# apple-mini.net
KiCad netlist of a schematic drawn in EAGLE
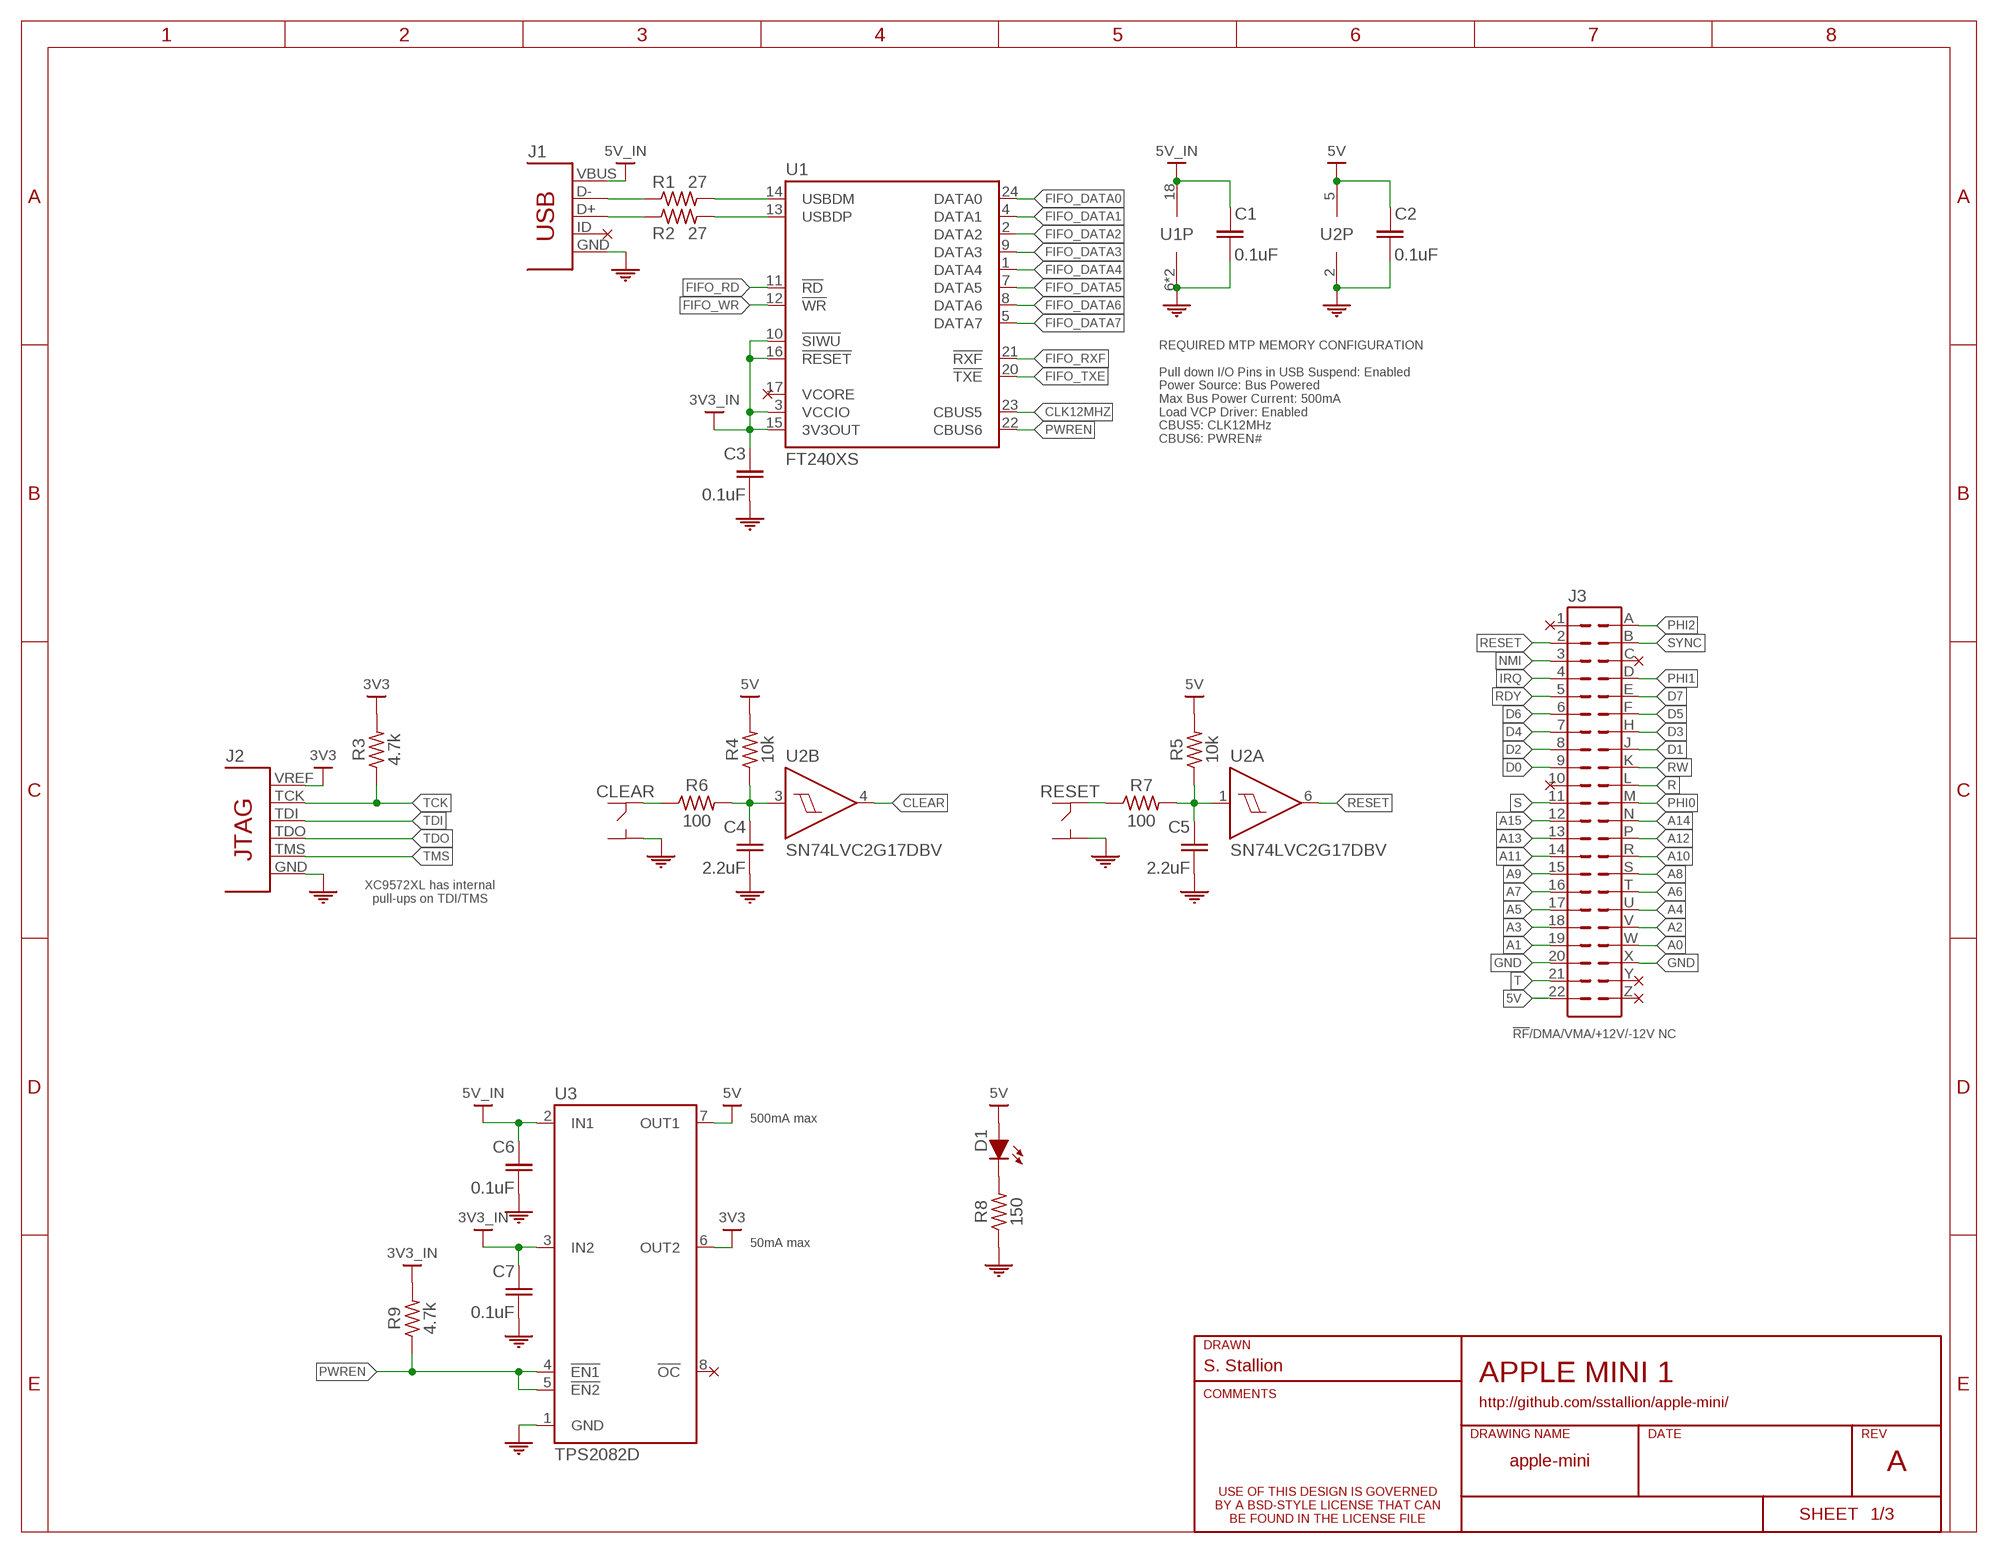
[diagram p0: schematic, sheet 1]
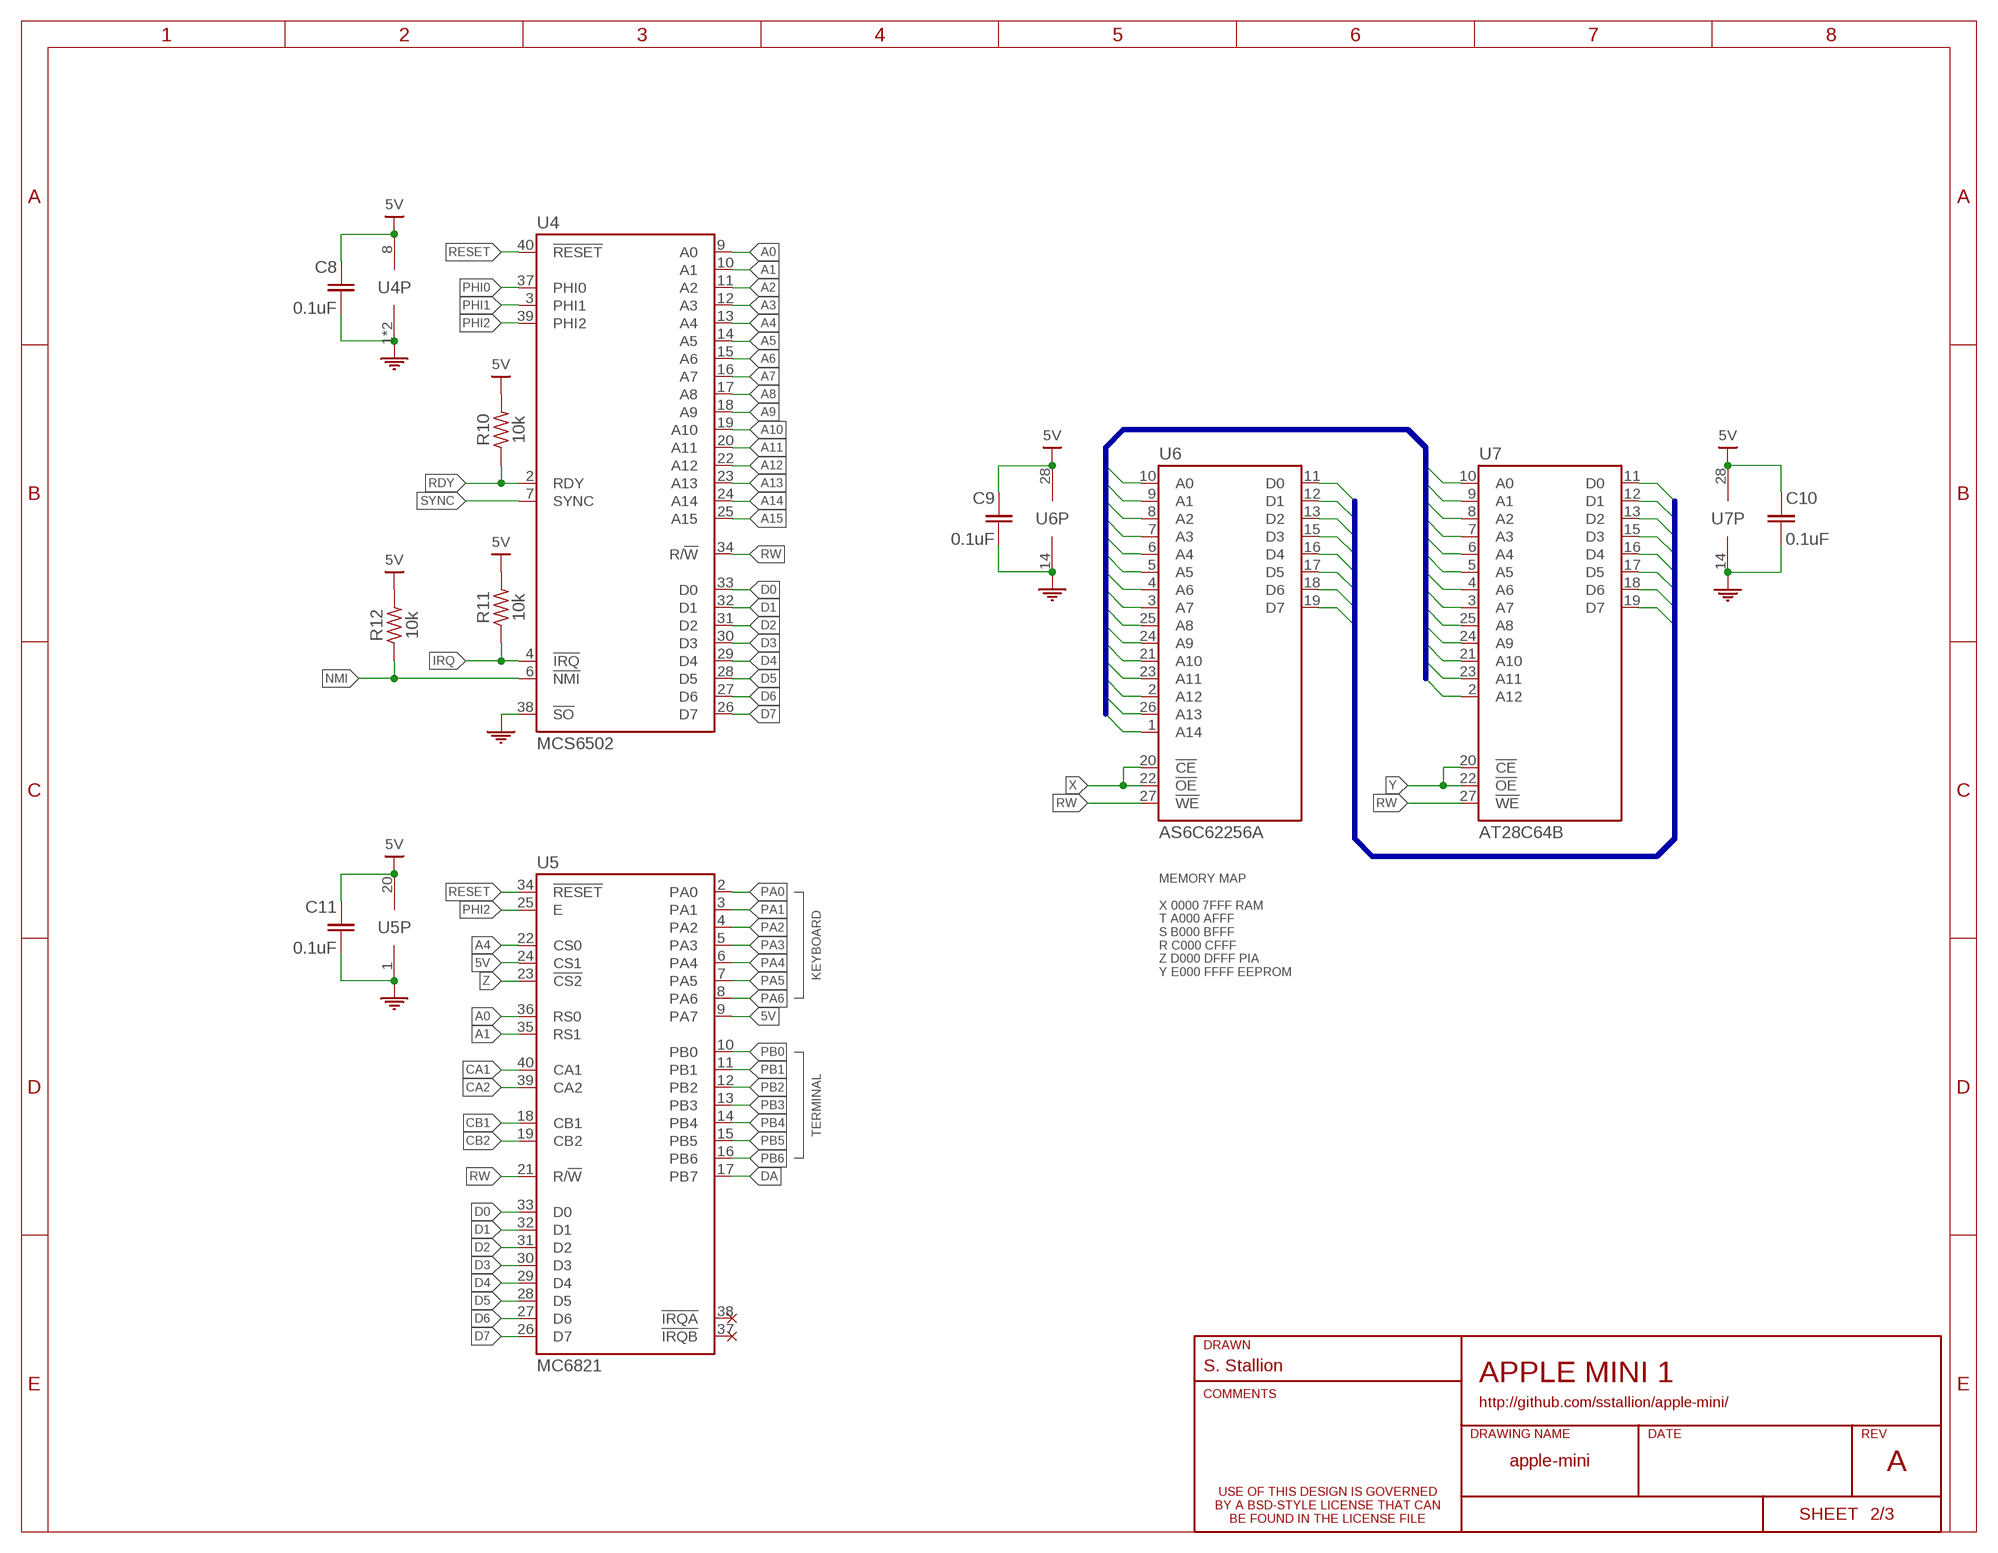
[diagram p1: schematic, sheet 2]
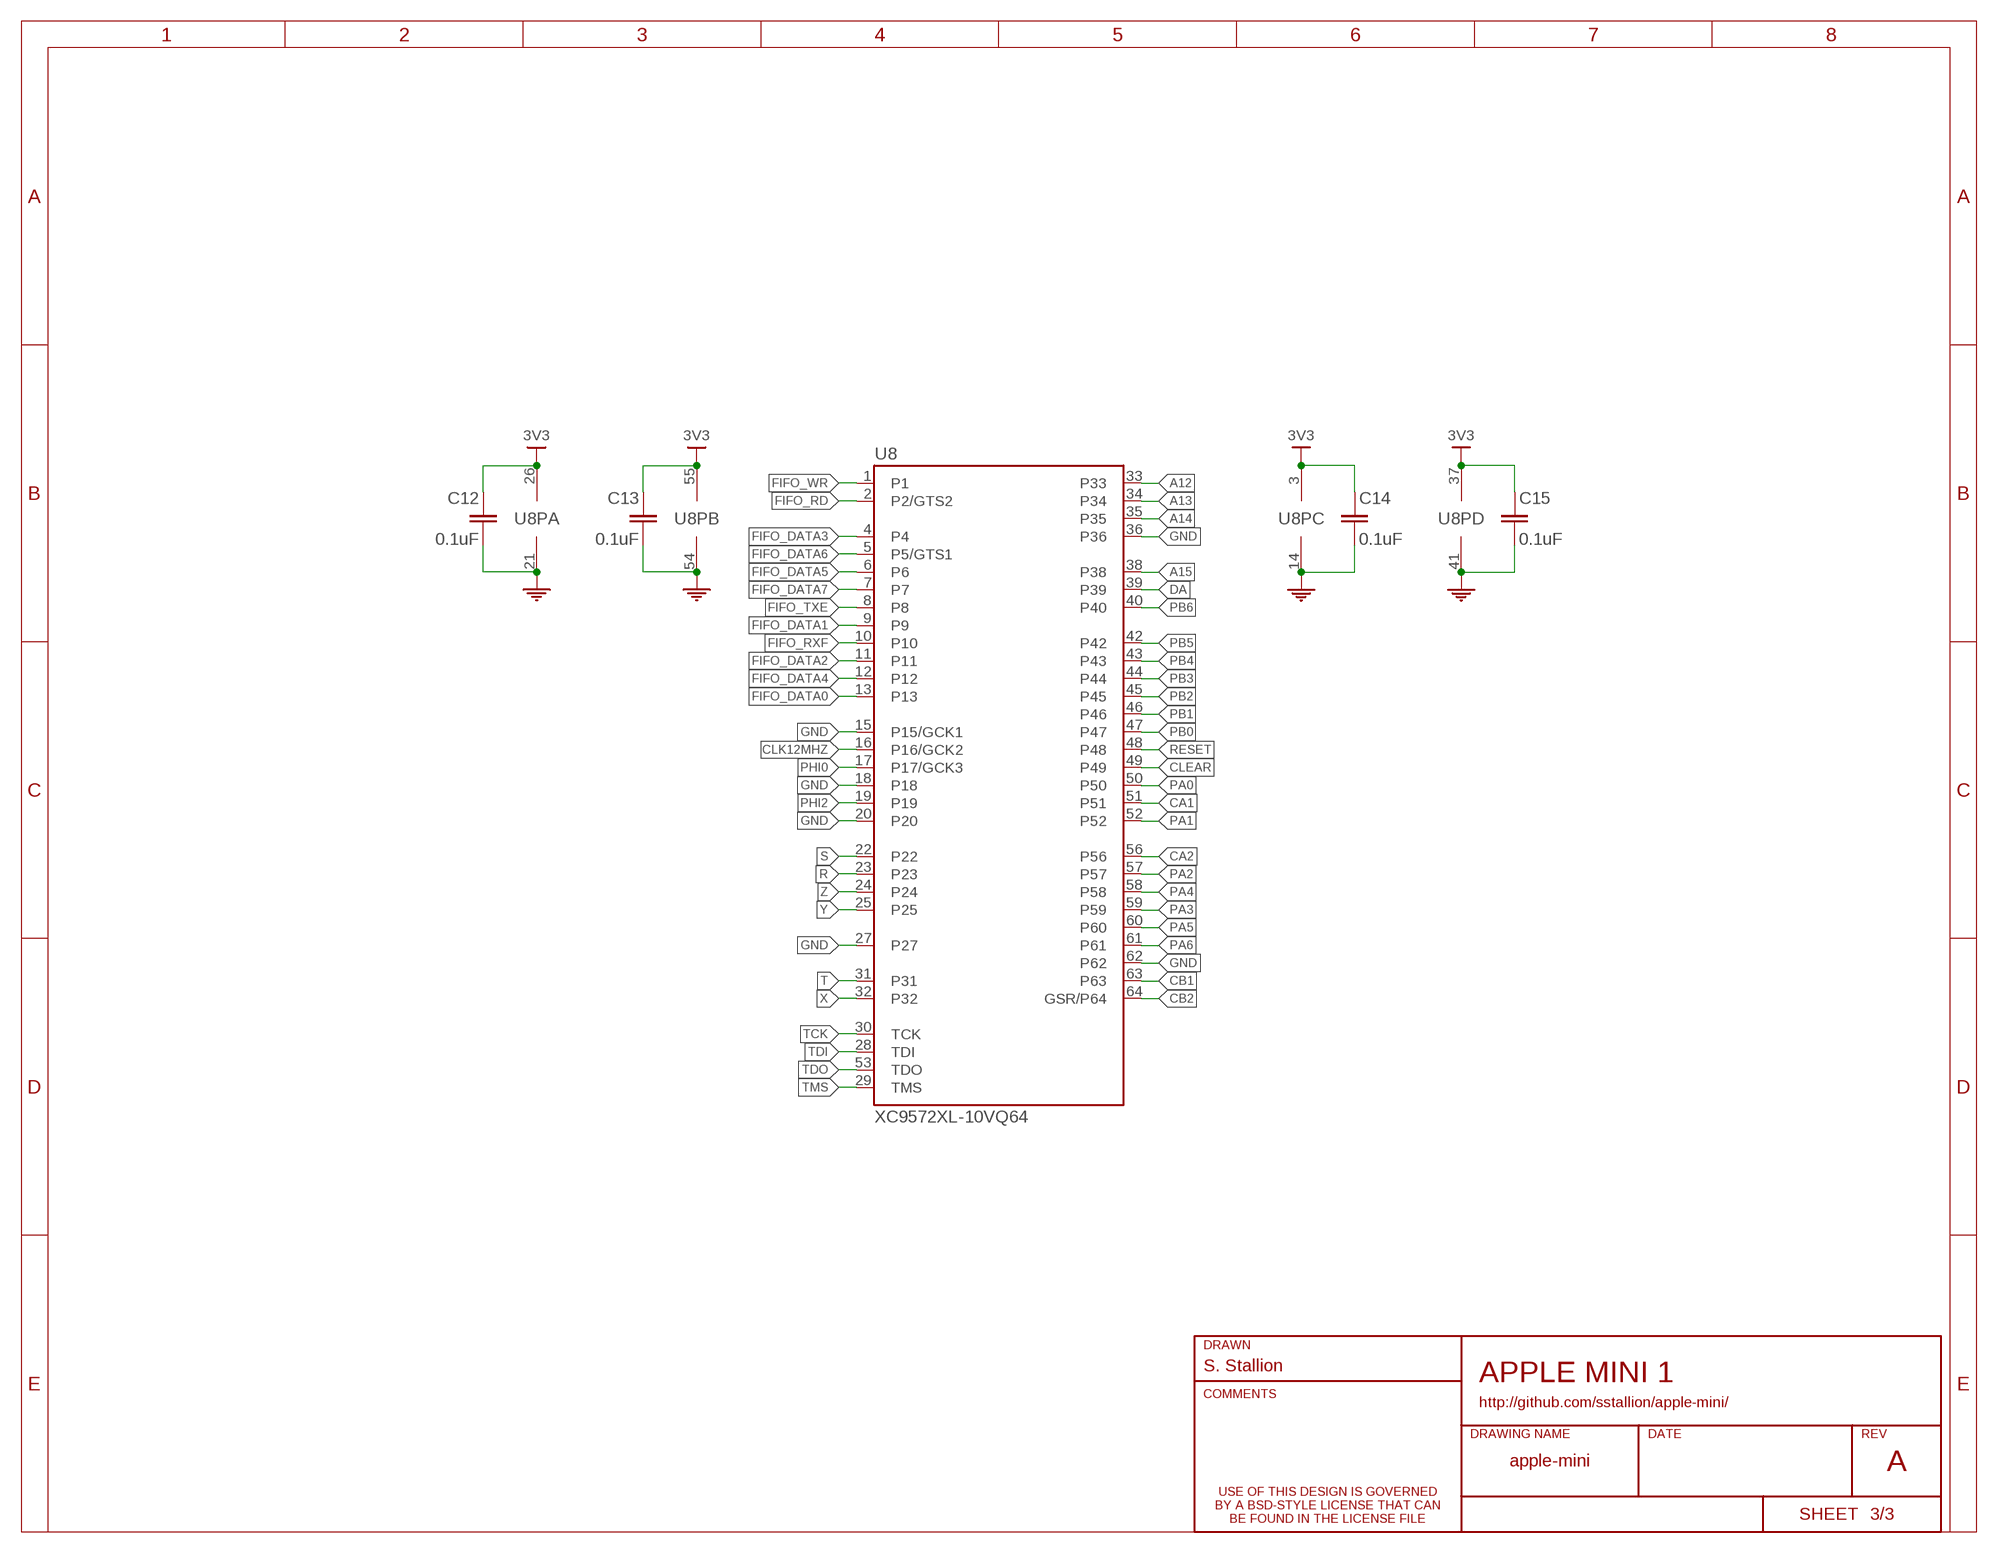
[diagram p2: schematic, sheet 3]

(export (version "E")
  (design (tool "Eeschema 10.0.6"))
  (components
    (comp (ref "C12")
      (value "0.1uF")
      (footprint "eagle-import:0603")
      (fields
        (field (name "COMMENTS") "16V 10% X7R MLCC")
        (field (name "MFR") "Kemet")
        (field (name "MFR_PARTNO") "C0603C104K4RACTU")
        (field (name "VENDOR") "Digi-Key")
        (field (name "VENDOR_PARTNO") "399-1096-1-ND")
      )
      (libsource (lib "eagle-import") (part "C0603"))
    )
    (comp (ref "C13")
      (value "0.1uF")
      (footprint "eagle-import:0603")
      (fields
        (field (name "COMMENTS") "16V 10% X7R MLCC")
        (field (name "MFR") "Kemet")
        (field (name "MFR_PARTNO") "C0603C104K4RACTU")
        (field (name "VENDOR") "Digi-Key")
        (field (name "VENDOR_PARTNO") "399-1096-1-ND")
      )
      (libsource (lib "eagle-import") (part "C0603"))
    )
    (comp (ref "C14")
      (value "0.1uF")
      (footprint "eagle-import:0603")
      (fields
        (field (name "COMMENTS") "16V 10% X7R MLCC")
        (field (name "MFR") "Kemet")
        (field (name "MFR_PARTNO") "C0603C104K4RACTU")
        (field (name "VENDOR") "Digi-Key")
        (field (name "VENDOR_PARTNO") "399-1096-1-ND")
      )
      (libsource (lib "eagle-import") (part "C0603"))
    )
    (comp (ref "C15")
      (value "0.1uF")
      (footprint "eagle-import:0603")
      (fields
        (field (name "COMMENTS") "16V 10% X7R MLCC")
        (field (name "MFR") "Kemet")
        (field (name "MFR_PARTNO") "C0603C104K4RACTU")
        (field (name "VENDOR") "Digi-Key")
        (field (name "VENDOR_PARTNO") "399-1096-1-ND")
      )
      (libsource (lib "eagle-import") (part "C0603"))
    )
    (comp (ref "U8")
      (value "XC9572XL-10VQ64")
      (footprint "eagle-import:VQFP64")
      (fields
        (field (name "MFR") "Xilinx")
        (field (name "MFR_PARTNO") "XC9572XL-10VQG64C")
        (field (name "VENDOR") "Digi-Key")
        (field (name "VENDOR_PARTNO") "122-1388-ND")
      )
      (libsource (lib "eagle-import") (part "XC9572XL-VQ6410"))
    )
    (comp (ref "C8")
      (value "0.1uF")
      (footprint "eagle-import:0603")
      (fields
        (field (name "COMMENTS") "16V 10% X7R MLCC")
        (field (name "MFR") "Kemet")
        (field (name "MFR_PARTNO") "C0603C104K4RACTU")
        (field (name "VENDOR") "Digi-Key")
        (field (name "VENDOR_PARTNO") "399-1096-1-ND")
      )
      (libsource (lib "eagle-import") (part "C0603"))
    )
    (comp (ref "C9")
      (value "0.1uF")
      (footprint "eagle-import:0603")
      (fields
        (field (name "COMMENTS") "16V 10% X7R MLCC")
        (field (name "MFR") "Kemet")
        (field (name "MFR_PARTNO") "C0603C104K4RACTU")
        (field (name "VENDOR") "Digi-Key")
        (field (name "VENDOR_PARTNO") "399-1096-1-ND")
      )
      (libsource (lib "eagle-import") (part "C0603"))
    )
    (comp (ref "C10")
      (value "0.1uF")
      (footprint "eagle-import:0603")
      (fields
        (field (name "COMMENTS") "16V 10% X7R MLCC")
        (field (name "MFR") "Kemet")
        (field (name "MFR_PARTNO") "C0603C104K4RACTU")
        (field (name "VENDOR") "Digi-Key")
        (field (name "VENDOR_PARTNO") "399-1096-1-ND")
      )
      (libsource (lib "eagle-import") (part "C0603"))
    )
    (comp (ref "C11")
      (value "0.1uF")
      (footprint "eagle-import:0603")
      (fields
        (field (name "COMMENTS") "16V 10% X7R MLCC")
        (field (name "MFR") "Kemet")
        (field (name "MFR_PARTNO") "C0603C104K4RACTU")
        (field (name "VENDOR") "Digi-Key")
        (field (name "VENDOR_PARTNO") "399-1096-1-ND")
      )
      (libsource (lib "eagle-import") (part "C0603"))
    )
    (comp (ref "R10")
      (value "10k")
      (footprint "eagle-import:0603")
      (fields
        (field (name "COMMENTS") "5% 1/10W")
        (field (name "MFR") "Yageo")
        (field (name "MFR_PARTNO") "RC0603JR-0710KL")
        (field (name "VENDOR") "Digi-Key")
        (field (name "VENDOR_PARTNO") "311-10KGRCT-ND")
      )
      (libsource (lib "eagle-import") (part "R0603"))
    )
    (comp (ref "R11")
      (value "10k")
      (footprint "eagle-import:0603")
      (fields
        (field (name "COMMENTS") "5% 1/10W")
        (field (name "MFR") "Yageo")
        (field (name "MFR_PARTNO") "RC0603JR-0710KL")
        (field (name "VENDOR") "Digi-Key")
        (field (name "VENDOR_PARTNO") "311-10KGRCT-ND")
      )
      (libsource (lib "eagle-import") (part "R0603"))
    )
    (comp (ref "R12")
      (value "10k")
      (footprint "eagle-import:0603")
      (fields
        (field (name "COMMENTS") "5% 1/10W")
        (field (name "MFR") "Yageo")
        (field (name "MFR_PARTNO") "RC0603JR-0710KL")
        (field (name "VENDOR") "Digi-Key")
        (field (name "VENDOR_PARTNO") "311-10KGRCT-ND")
      )
      (libsource (lib "eagle-import") (part "R0603"))
    )
    (comp (ref "U4")
      (value "MCS6502")
      (footprint "eagle-import:DIP40")
      (fields
        (field (name "MFR") "MOS Technology")
        (field (name "VENDOR") "Jameco")
        (field (name "VENDOR_PARTNO") "43191")
      )
      (libsource (lib "eagle-import") (part "MCS6502"))
    )
    (comp (ref "U5")
      (value "MC6821")
      (footprint "eagle-import:DIP40")
      (fields
        (field (name "MFR") "Motorola")
        (field (name "VENDOR") "Jameco")
        (field (name "VENDOR_PARTNO") "43596")
      )
      (libsource (lib "eagle-import") (part "MC6821"))
    )
    (comp (ref "U6")
      (value "AS6C62256A")
      (footprint "eagle-import:DIP28")
      (fields
        (field (name "MFR") "Alliance Memory")
        (field (name "MFR_PARTNO") "AS6C62256A-70PCN")
        (field (name "VENDOR") "Digi-Key")
        (field (name "VENDOR_PARTNO") "1450-1182-5-ND")
      )
      (libsource (lib "eagle-import") (part "AS6C62256A"))
    )
    (comp (ref "U7")
      (value "AT28C64B")
      (footprint "eagle-import:DIP28")
      (fields
        (field (name "MFR") "Atmel")
        (field (name "MFR_PARTNO") "AT28C64B-15PU")
        (field (name "VENDOR") "Digi-Key")
        (field (name "VENDOR_PARTNO") "AT28C64B-15PU-ND")
      )
      (libsource (lib "eagle-import") (part "AT28C64B"))
    )
    (comp (ref "C1")
      (value "0.1uF")
      (footprint "eagle-import:0603")
      (fields
        (field (name "COMMENTS") "16V 10% X7R MLCC")
        (field (name "MFR") "Kemet")
        (field (name "MFR_PARTNO") "C0603C104K4RACTU")
        (field (name "VENDOR") "Digi-Key")
        (field (name "VENDOR_PARTNO") "399-1096-1-ND")
      )
      (libsource (lib "eagle-import") (part "C0603"))
    )
    (comp (ref "C2")
      (value "0.1uF")
      (footprint "eagle-import:0603")
      (fields
        (field (name "COMMENTS") "16V 10% X7R MLCC")
        (field (name "MFR") "Kemet")
        (field (name "MFR_PARTNO") "C0603C104K4RACTU")
        (field (name "VENDOR") "Digi-Key")
        (field (name "VENDOR_PARTNO") "399-1096-1-ND")
      )
      (libsource (lib "eagle-import") (part "C0603"))
    )
    (comp (ref "C3")
      (value "0.1uF")
      (footprint "eagle-import:0603")
      (fields
        (field (name "COMMENTS") "16V 10% X7R MLCC")
        (field (name "MFR") "Kemet")
        (field (name "MFR_PARTNO") "C0603C104K4RACTU")
        (field (name "VENDOR") "Digi-Key")
        (field (name "VENDOR_PARTNO") "399-1096-1-ND")
      )
      (libsource (lib "eagle-import") (part "C0603"))
    )
    (comp (ref "C4")
      (value "2.2uF")
      (footprint "eagle-import:0603")
      (fields
        (field (name "COMMENTS") "16V 10% X5R MLCC")
        (field (name "MFR") "Kemet")
        (field (name "MFR_PARTNO") "C0603C225K4PACTU")
        (field (name "VENDOR") "Digi-Key")
        (field (name "VENDOR_PARTNO") "399-7886-1-ND")
      )
      (libsource (lib "eagle-import") (part "C0603"))
    )
    (comp (ref "C5")
      (value "2.2uF")
      (footprint "eagle-import:0603")
      (fields
        (field (name "COMMENTS") "16V 10% X5R MLCC")
        (field (name "MFR") "Kemet")
        (field (name "MFR_PARTNO") "C0603C225K4PACTU")
        (field (name "VENDOR") "Digi-Key")
        (field (name "VENDOR_PARTNO") "399-7886-1-ND")
      )
      (libsource (lib "eagle-import") (part "C0603"))
    )
    (comp (ref "C6")
      (value "0.1uF")
      (footprint "eagle-import:0603")
      (fields
        (field (name "COMMENTS") "16V 10% X7R MLCC")
        (field (name "MFR") "Kemet")
        (field (name "MFR_PARTNO") "C0603C104K4RACTU")
        (field (name "VENDOR") "Digi-Key")
        (field (name "VENDOR_PARTNO") "399-1096-1-ND")
      )
      (libsource (lib "eagle-import") (part "C0603"))
    )
    (comp (ref "C7")
      (value "0.1uF")
      (footprint "eagle-import:0603")
      (fields
        (field (name "COMMENTS") "16V 10% X7R MLCC")
        (field (name "MFR") "Kemet")
        (field (name "MFR_PARTNO") "C0603C104K4RACTU")
        (field (name "VENDOR") "Digi-Key")
        (field (name "VENDOR_PARTNO") "399-1096-1-ND")
      )
      (libsource (lib "eagle-import") (part "C0603"))
    )
    (comp (ref "CLEAR")
      (value "TACTSW")
      (footprint "eagle-import:SMTR92")
      (fields
        (field (name "MFR") "C&K Components")
        (field (name "MFR_PARTNO") "PTS645SL50SMTR92 LFS")
        (field (name "COMMENTS") "12V 50mA")
        (field (name "VENDOR") "Digi-Key")
        (field (name "VENDOR_PARTNO") "CKN9088CT-ND")
      )
      (libsource (lib "eagle-import") (part "TACTSW"))
    )
    (comp (ref "D1")
      (value "CHIPLED")
      (footprint "eagle-import:0603")
      (fields
        (field (name "COMMENTS") "2.0-2.5V 20mA")
        (field (name "MFR") "Lite-On")
        (field (name "MFR_PARTNO") "LTST-C190KGKT")
        (field (name "VENDOR") "Digi-Key")
        (field (name "VENDOR_PARTNO") "160-1435-1-ND")
      )
      (libsource (lib "eagle-import") (part "CHIPLED"))
    )
    (comp (ref "J1")
      (value "USBMICRO")
      (footprint "eagle-import:10118193-0001LF")
      (fields
        (field (name "MFR") "FCI")
        (field (name "MFR_PARTNO") "10118193-0001LF")
        (field (name "VENDOR") "Digi-Key")
        (field (name "VENDOR_PARTNO") "609-4616-1-ND")
      )
      (libsource (lib "eagle-import") (part "USBMICRO"))
    )
    (comp (ref "J2")
      (value "JTAG")
      (footprint "eagle-import:PH07-2-SMT")
      (fields
        (field (name "MFR") "Molex")
        (field (name "MFR_PARTNO") "0878321420")
        (field (name "VENDOR") "Digi-Key")
        (field (name "VENDOR_PARTNO") "WM18641-ND")
      )
      (libsource (lib "eagle-import") (part "JTAG"))
    )
    (comp (ref "J3")
      (value "RBM22DRTN")
      (footprint "eagle-import:M22DRTN")
      (fields
        (field (name "MFR") "Sullins")
        (field (name "VENDOR") "Digi-Key")
        (field (name "VENDOR_PARTNO") "RBM22DRTN-ND")
      )
      (libsource (lib "eagle-import") (part "M22DRTNRB"))
    )
    (comp (ref "R1")
      (value "27")
      (footprint "eagle-import:0402")
      (fields
        (field (name "COMMENTS") "5% 1/16W")
        (field (name "MFR") "Yageo")
        (field (name "MFR_PARTNO") "RC0402JR-0727RL")
        (field (name "VENDOR") "Digi-Key")
        (field (name "VENDOR_PARTNO") "311-27JRCT-ND")
      )
      (libsource (lib "eagle-import") (part "R0402"))
    )
    (comp (ref "R2")
      (value "27")
      (footprint "eagle-import:0402")
      (fields
        (field (name "COMMENTS") "5% 1/16W")
        (field (name "MFR") "Yageo")
        (field (name "MFR_PARTNO") "RC0402JR-0727RL")
        (field (name "VENDOR") "Digi-Key")
        (field (name "VENDOR_PARTNO") "311-27JRCT-ND")
      )
      (libsource (lib "eagle-import") (part "R0402"))
    )
    (comp (ref "R3")
      (value "4.7k")
      (footprint "eagle-import:0603")
      (fields
        (field (name "COMMENTS") "5% 1/10W")
        (field (name "MFR") "Yageo")
        (field (name "MFR_PARTNO") "RC0603JR-074K7L")
        (field (name "VENDOR") "Digi-Key")
        (field (name "VENDOR_PARTNO") "311-4.7KGRCT-ND")
      )
      (libsource (lib "eagle-import") (part "R0603"))
    )
    (comp (ref "R4")
      (value "10k")
      (footprint "eagle-import:0603")
      (fields
        (field (name "COMMENTS") "5% 1/10W")
        (field (name "MFR") "Yageo")
        (field (name "MFR_PARTNO") "RC0603JR-0710KL")
        (field (name "VENDOR") "Digi-Key")
        (field (name "VENDOR_PARTNO") "311-10KGRCT-ND")
      )
      (libsource (lib "eagle-import") (part "R0603"))
    )
    (comp (ref "R5")
      (value "10k")
      (footprint "eagle-import:0603")
      (fields
        (field (name "COMMENTS") "5% 1/10W")
        (field (name "MFR") "Yageo")
        (field (name "MFR_PARTNO") "RC0603JR-0710KL")
        (field (name "VENDOR") "Digi-Key")
        (field (name "VENDOR_PARTNO") "311-10KGRCT-ND")
      )
      (libsource (lib "eagle-import") (part "R0603"))
    )
    (comp (ref "R6")
      (value "100")
      (footprint "eagle-import:0603")
      (fields
        (field (name "MFR") "Rohm Semiconductor")
        (field (name "MFR_PARTNO") "ESR03EZPJ101")
        (field (name "VENDOR_PARTNO") "RHM100DCT-ND")
      )
      (libsource (lib "eagle-import") (part "R0603"))
    )
    (comp (ref "R7")
      (value "100")
      (footprint "eagle-import:0603")
      (fields
        (field (name "COMMENTS") "5% 1/4W")
        (field (name "MFR") "Rohm Semiconductor")
        (field (name "MFR_PARTNO") "ESR03EZPJ101")
        (field (name "VENDOR") "Digi-Key")
        (field (name "VENDOR_PARTNO") "RHM100DCT-ND")
      )
      (libsource (lib "eagle-import") (part "R0603"))
    )
    (comp (ref "R8")
      (value "150")
      (footprint "eagle-import:0603")
      (fields
        (field (name "COMMENTS") "5% 1/4W")
        (field (name "MFR") "Rohm Semiconductor")
        (field (name "MFR_PARTNO") "ESR03EZPJ181")
        (field (name "VENDOR") "Digi-Key")
        (field (name "VENDOR_PARTNO") "RHM180DCT-ND")
      )
      (libsource (lib "eagle-import") (part "R0603"))
    )
    (comp (ref "R9")
      (value "4.7k")
      (footprint "eagle-import:0603")
      (fields
        (field (name "COMMENTS") "5% 1/10W")
        (field (name "MFR") "Yageo")
        (field (name "MFR_PARTNO") "RC0603JR-074K7L")
        (field (name "VENDOR") "Digi-Key")
        (field (name "VENDOR_PARTNO") "311-4.7KGRCT-ND")
      )
      (libsource (lib "eagle-import") (part "R0603"))
    )
    (comp (ref "RESET")
      (value "TACTSW")
      (footprint "eagle-import:SMTR92")
      (fields
        (field (name "MFR") "C&K Components")
        (field (name "MFR_PARTNO") "PTS645SL50SMTR92 LFS")
        (field (name "COMMENTS") "12V 50mA")
        (field (name "VENDOR") "Digi-Key")
        (field (name "VENDOR_PARTNO") "CKN9088CT-ND")
      )
      (libsource (lib "eagle-import") (part "TACTSW"))
    )
    (comp (ref "U1")
      (value "FT240XS")
      (footprint "eagle-import:SSOP24")
      (fields
        (field (name "MFR") "FTDI")
        (field (name "MFR_PARTNO") "FT240XS-U")
        (field (name "VENDOR") "Digi-Key")
        (field (name "VENDOR_PARTNO") "768-1158-5-ND")
      )
      (libsource (lib "eagle-import") (part "FT240XS"))
    )
    (comp (ref "U2")
      (value "SN74LVC2G17DBV")
      (footprint "eagle-import:SOT23-6")
      (fields
        (field (name "MFR") "Texas Instruments")
        (field (name "MFR_PARTNO") "SN74LVC2G17DBVR")
        (field (name "VENDOR") "Digi-Key")
        (field (name "VENDOR_PARTNO") "296-13012-1-ND")
      )
      (libsource (lib "eagle-import") (part "SN74LVC2G17DBV"))
    )
    (comp (ref "U3")
      (value "TPS2082D")
      (footprint "eagle-import:SOIC8")
      (fields
        (field (name "MFR") "Texas Instruments")
        (field (name "VENDOR") "Digi-Key")
        (field (name "VENDOR_PARTNO") "296-3433-5-ND")
      )
      (libsource (lib "eagle-import") (part "TPS2082D"))
    )
  )
  (nets
    (net (code "1") (name "3V3") (class "Default")
      (node (ref "C12") (pin "1") (pinfunction "1_1") (pintype "passive"))
      (node (ref "C13") (pin "1") (pinfunction "1_1") (pintype "passive"))
      (node (ref "C14") (pin "1") (pinfunction "1_1") (pintype "passive"))
      (node (ref "C15") (pin "1") (pinfunction "1_1") (pintype "passive"))
      (node (ref "J2") (pin "2") (pinfunction "VREF_2") (pintype "power_in"))
      (node (ref "R3") (pin "2") (pinfunction "2_2") (pintype "passive"))
      (node (ref "U3") (pin "6") (pinfunction "OUT2_6") (pintype "power_in"))
      (node (ref "U8") (pin "26") (pinfunction "VCC_26") (pintype "power_in"))
      (node (ref "U8") (pin "3") (pinfunction "VCC_3") (pintype "power_in"))
      (node (ref "U8") (pin "37") (pinfunction "VCC_37") (pintype "power_in"))
      (node (ref "U8") (pin "55") (pinfunction "VCC_55") (pintype "power_in"))
    )
    (net (code "2") (name "3V3_IN") (class "Default")
      (node (ref "C3") (pin "1") (pinfunction "1_1") (pintype "passive"))
      (node (ref "C7") (pin "1") (pinfunction "1_1") (pintype "passive"))
      (node (ref "R9") (pin "2") (pinfunction "2_2") (pintype "passive"))
      (node (ref "U1") (pin "10") (pinfunction "~{SIWU}_10") (pintype "input"))
      (node (ref "U1") (pin "15") (pinfunction "3V3OUT_15") (pintype "power_in"))
      (node (ref "U1") (pin "16") (pinfunction "~{RESET}_16") (pintype "input"))
      (node (ref "U1") (pin "3") (pinfunction "VCCIO_3") (pintype "power_in"))
      (node (ref "U3") (pin "3") (pinfunction "IN2_3") (pintype "power_in"))
    )
    (net (code "3") (name "5V") (class "Default")
      (node (ref "C10") (pin "1") (pinfunction "1_1") (pintype "passive"))
      (node (ref "C11") (pin "1") (pinfunction "1_1") (pintype "passive"))
      (node (ref "C2") (pin "1") (pinfunction "1_1") (pintype "passive"))
      (node (ref "C8") (pin "1") (pinfunction "1_1") (pintype "passive"))
      (node (ref "C9") (pin "1") (pinfunction "1_1") (pintype "passive"))
      (node (ref "D1") (pin "2") (pinfunction "2_2") (pintype "passive"))
      (node (ref "J3") (pin "22") (pinfunction "22_22") (pintype "passive"))
      (node (ref "R10") (pin "2") (pinfunction "2_2") (pintype "passive"))
      (node (ref "R11") (pin "2") (pinfunction "2_2") (pintype "passive"))
      (node (ref "R12") (pin "2") (pinfunction "2_2") (pintype "passive"))
      (node (ref "R4") (pin "2") (pinfunction "2_2") (pintype "passive"))
      (node (ref "R5") (pin "2") (pinfunction "2_2") (pintype "passive"))
      (node (ref "U2") (pin "5") (pinfunction "VCC_5") (pintype "power_in"))
      (node (ref "U3") (pin "7") (pinfunction "OUT1_7") (pintype "power_in"))
      (node (ref "U4") (pin "8") (pinfunction "VCC_8") (pintype "power_in"))
      (node (ref "U5") (pin "20") (pinfunction "VCC_20") (pintype "power_in"))
      (node (ref "U5") (pin "24") (pinfunction "CS1_24") (pintype "input"))
      (node (ref "U5") (pin "9") (pinfunction "PA7_9") (pintype "bidirectional"))
      (node (ref "U6") (pin "28") (pinfunction "VCC_28") (pintype "power_in"))
      (node (ref "U7") (pin "28") (pinfunction "VCC_28") (pintype "power_in"))
    )
    (net (code "4") (name "5V_IN") (class "Default")
      (node (ref "C1") (pin "1") (pinfunction "1_1") (pintype "passive"))
      (node (ref "C6") (pin "1") (pinfunction "1_1") (pintype "passive"))
      (node (ref "J1") (pin "1") (pinfunction "1_1") (pintype "power_in"))
      (node (ref "U1") (pin "18") (pinfunction "VCC_18") (pintype "power_in"))
      (node (ref "U3") (pin "2") (pinfunction "IN1_2") (pintype "power_in"))
    )
    (net (code "5") (name "A0") (class "Default")
      (node (ref "J3") (pin "W") (pinfunction "W_W") (pintype "passive"))
      (node (ref "U4") (pin "9") (pinfunction "A0_9") (pintype "output"))
      (node (ref "U5") (pin "36") (pinfunction "RS0_36") (pintype "input"))
      (node (ref "U6") (pin "10") (pinfunction "A0_10") (pintype "input"))
      (node (ref "U7") (pin "10") (pinfunction "A0_10") (pintype "input"))
    )
    (net (code "6") (name "A1") (class "Default")
      (node (ref "J3") (pin "19") (pinfunction "19_19") (pintype "passive"))
      (node (ref "U4") (pin "10") (pinfunction "A1_10") (pintype "output"))
      (node (ref "U5") (pin "35") (pinfunction "RS1_35") (pintype "input"))
      (node (ref "U6") (pin "9") (pinfunction "A1_9") (pintype "input"))
      (node (ref "U7") (pin "9") (pinfunction "A1_9") (pintype "input"))
    )
    (net (code "7") (name "A2") (class "Default")
      (node (ref "J3") (pin "V") (pinfunction "V_V") (pintype "passive"))
      (node (ref "U4") (pin "11") (pinfunction "A2_11") (pintype "output"))
      (node (ref "U6") (pin "8") (pinfunction "A2_8") (pintype "input"))
      (node (ref "U7") (pin "8") (pinfunction "A2_8") (pintype "input"))
    )
    (net (code "8") (name "A3") (class "Default")
      (node (ref "J3") (pin "18") (pinfunction "18_18") (pintype "passive"))
      (node (ref "U4") (pin "12") (pinfunction "A3_12") (pintype "output"))
      (node (ref "U6") (pin "7") (pinfunction "A3_7") (pintype "input"))
      (node (ref "U7") (pin "7") (pinfunction "A3_7") (pintype "input"))
    )
    (net (code "9") (name "A4") (class "Default")
      (node (ref "J3") (pin "U") (pinfunction "U_U") (pintype "passive"))
      (node (ref "U4") (pin "13") (pinfunction "A4_13") (pintype "output"))
      (node (ref "U5") (pin "22") (pinfunction "CS0_22") (pintype "input"))
      (node (ref "U6") (pin "6") (pinfunction "A4_6") (pintype "input"))
      (node (ref "U7") (pin "6") (pinfunction "A4_6") (pintype "input"))
    )
    (net (code "10") (name "A5") (class "Default")
      (node (ref "J3") (pin "17") (pinfunction "17_17") (pintype "passive"))
      (node (ref "U4") (pin "14") (pinfunction "A5_14") (pintype "output"))
      (node (ref "U6") (pin "5") (pinfunction "A5_5") (pintype "input"))
      (node (ref "U7") (pin "5") (pinfunction "A5_5") (pintype "input"))
    )
    (net (code "11") (name "A6") (class "Default")
      (node (ref "J3") (pin "T") (pinfunction "T_T") (pintype "passive"))
      (node (ref "U4") (pin "15") (pinfunction "A6_15") (pintype "output"))
      (node (ref "U6") (pin "4") (pinfunction "A6_4") (pintype "input"))
      (node (ref "U7") (pin "4") (pinfunction "A6_4") (pintype "input"))
    )
    (net (code "12") (name "A7") (class "Default")
      (node (ref "J3") (pin "16") (pinfunction "16_16") (pintype "passive"))
      (node (ref "U4") (pin "16") (pinfunction "A7_16") (pintype "output"))
      (node (ref "U6") (pin "3") (pinfunction "A7_3") (pintype "input"))
      (node (ref "U7") (pin "3") (pinfunction "A7_3") (pintype "input"))
    )
    (net (code "13") (name "A8") (class "Default")
      (node (ref "J3") (pin "S") (pinfunction "S_S") (pintype "passive"))
      (node (ref "U4") (pin "17") (pinfunction "A8_17") (pintype "output"))
      (node (ref "U6") (pin "25") (pinfunction "A8_25") (pintype "input"))
      (node (ref "U7") (pin "25") (pinfunction "A8_25") (pintype "input"))
    )
    (net (code "14") (name "A9") (class "Default")
      (node (ref "J3") (pin "15") (pinfunction "15_15") (pintype "passive"))
      (node (ref "U4") (pin "18") (pinfunction "A9_18") (pintype "output"))
      (node (ref "U6") (pin "24") (pinfunction "A9_24") (pintype "input"))
      (node (ref "U7") (pin "24") (pinfunction "A9_24") (pintype "input"))
    )
    (net (code "15") (name "A10") (class "Default")
      (node (ref "J3") (pin "R") (pinfunction "R_R") (pintype "passive"))
      (node (ref "U4") (pin "19") (pinfunction "A10_19") (pintype "output"))
      (node (ref "U6") (pin "21") (pinfunction "A10_21") (pintype "input"))
      (node (ref "U7") (pin "21") (pinfunction "A10_21") (pintype "input"))
    )
    (net (code "16") (name "A11") (class "Default")
      (node (ref "J3") (pin "14") (pinfunction "14_14") (pintype "passive"))
      (node (ref "U4") (pin "20") (pinfunction "A11_20") (pintype "output"))
      (node (ref "U6") (pin "23") (pinfunction "A11_23") (pintype "input"))
      (node (ref "U7") (pin "23") (pinfunction "A11_23") (pintype "input"))
    )
    (net (code "17") (name "A12") (class "Default")
      (node (ref "J3") (pin "P") (pinfunction "P_P") (pintype "passive"))
      (node (ref "U4") (pin "22") (pinfunction "A12_22") (pintype "output"))
      (node (ref "U6") (pin "2") (pinfunction "A12_2") (pintype "input"))
      (node (ref "U7") (pin "2") (pinfunction "A12_2") (pintype "input"))
      (node (ref "U8") (pin "33") (pinfunction "P33_33") (pintype "bidirectional"))
    )
    (net (code "18") (name "A13") (class "Default")
      (node (ref "J3") (pin "13") (pinfunction "13_13") (pintype "passive"))
      (node (ref "U4") (pin "23") (pinfunction "A13_23") (pintype "output"))
      (node (ref "U6") (pin "26") (pinfunction "A13_26") (pintype "input"))
      (node (ref "U8") (pin "34") (pinfunction "P34_34") (pintype "bidirectional"))
    )
    (net (code "19") (name "A14") (class "Default")
      (node (ref "J3") (pin "N") (pinfunction "N_N") (pintype "passive"))
      (node (ref "U4") (pin "24") (pinfunction "A14_24") (pintype "output"))
      (node (ref "U6") (pin "1") (pinfunction "A14_1") (pintype "input"))
      (node (ref "U8") (pin "35") (pinfunction "P35_35") (pintype "bidirectional"))
    )
    (net (code "20") (name "A15") (class "Default")
      (node (ref "J3") (pin "12") (pinfunction "12_12") (pintype "passive"))
      (node (ref "U4") (pin "25") (pinfunction "A15_25") (pintype "output"))
      (node (ref "U8") (pin "38") (pinfunction "P38_38") (pintype "bidirectional"))
    )
    (net (code "21") (name "CA1") (class "Default")
      (node (ref "U5") (pin "40") (pinfunction "CA1_40") (pintype "input"))
      (node (ref "U8") (pin "51") (pinfunction "P51_51") (pintype "bidirectional"))
    )
    (net (code "22") (name "CA2") (class "Default")
      (node (ref "U5") (pin "39") (pinfunction "CA2_39") (pintype "bidirectional"))
      (node (ref "U8") (pin "56") (pinfunction "P56_56") (pintype "bidirectional"))
    )
    (net (code "23") (name "CB1") (class "Default")
      (node (ref "U5") (pin "18") (pinfunction "CB1_18") (pintype "input"))
      (node (ref "U8") (pin "63") (pinfunction "P63_63") (pintype "bidirectional"))
    )
    (net (code "24") (name "CB2") (class "Default")
      (node (ref "U5") (pin "19") (pinfunction "CB2_19") (pintype "bidirectional"))
      (node (ref "U8") (pin "64") (pinfunction "GSR/P64_64") (pintype "bidirectional"))
    )
    (net (code "25") (name "CLEAR") (class "Default")
      (node (ref "U2") (pin "4") (pinfunction "Y_4") (pintype "output"))
      (node (ref "U8") (pin "49") (pinfunction "P49_49") (pintype "bidirectional"))
    )
    (net (code "26") (name "CLK12MHZ") (class "Default")
      (node (ref "U1") (pin "23") (pinfunction "CBUS5_23") (pintype "bidirectional"))
      (node (ref "U8") (pin "16") (pinfunction "P16/GCK2_16") (pintype "bidirectional"))
    )
    (net (code "27") (name "D0") (class "Default")
      (node (ref "J3") (pin "9") (pinfunction "9_9") (pintype "passive"))
      (node (ref "U4") (pin "33") (pinfunction "D0_33") (pintype "bidirectional"))
      (node (ref "U5") (pin "33") (pinfunction "D0_33") (pintype "bidirectional"))
      (node (ref "U6") (pin "11") (pinfunction "D0_11") (pintype "bidirectional"))
      (node (ref "U7") (pin "11") (pinfunction "D0_11") (pintype "bidirectional"))
    )
    (net (code "28") (name "D1") (class "Default")
      (node (ref "J3") (pin "J") (pinfunction "J_J") (pintype "passive"))
      (node (ref "U4") (pin "32") (pinfunction "D1_32") (pintype "bidirectional"))
      (node (ref "U5") (pin "32") (pinfunction "D1_32") (pintype "bidirectional"))
      (node (ref "U6") (pin "12") (pinfunction "D1_12") (pintype "bidirectional"))
      (node (ref "U7") (pin "12") (pinfunction "D1_12") (pintype "bidirectional"))
    )
    (net (code "29") (name "D2") (class "Default")
      (node (ref "J3") (pin "8") (pinfunction "8_8") (pintype "passive"))
      (node (ref "U4") (pin "31") (pinfunction "D2_31") (pintype "bidirectional"))
      (node (ref "U5") (pin "31") (pinfunction "D2_31") (pintype "bidirectional"))
      (node (ref "U6") (pin "13") (pinfunction "D2_13") (pintype "bidirectional"))
      (node (ref "U7") (pin "13") (pinfunction "D2_13") (pintype "bidirectional"))
    )
    (net (code "30") (name "D3") (class "Default")
      (node (ref "J3") (pin "H") (pinfunction "H_H") (pintype "passive"))
      (node (ref "U4") (pin "30") (pinfunction "D3_30") (pintype "bidirectional"))
      (node (ref "U5") (pin "30") (pinfunction "D3_30") (pintype "bidirectional"))
      (node (ref "U6") (pin "15") (pinfunction "D3_15") (pintype "bidirectional"))
      (node (ref "U7") (pin "15") (pinfunction "D3_15") (pintype "bidirectional"))
    )
    (net (code "31") (name "D4") (class "Default")
      (node (ref "J3") (pin "7") (pinfunction "7_7") (pintype "passive"))
      (node (ref "U4") (pin "29") (pinfunction "D4_29") (pintype "bidirectional"))
      (node (ref "U5") (pin "29") (pinfunction "D4_29") (pintype "bidirectional"))
      (node (ref "U6") (pin "16") (pinfunction "D4_16") (pintype "bidirectional"))
      (node (ref "U7") (pin "16") (pinfunction "D4_16") (pintype "bidirectional"))
    )
    (net (code "32") (name "D5") (class "Default")
      (node (ref "J3") (pin "F") (pinfunction "F_F") (pintype "passive"))
      (node (ref "U4") (pin "28") (pinfunction "D5_28") (pintype "bidirectional"))
      (node (ref "U5") (pin "28") (pinfunction "D5_28") (pintype "bidirectional"))
      (node (ref "U6") (pin "17") (pinfunction "D5_17") (pintype "bidirectional"))
      (node (ref "U7") (pin "17") (pinfunction "D5_17") (pintype "bidirectional"))
    )
    (net (code "33") (name "D6") (class "Default")
      (node (ref "J3") (pin "6") (pinfunction "6_6") (pintype "passive"))
      (node (ref "U4") (pin "27") (pinfunction "D6_27") (pintype "bidirectional"))
      (node (ref "U5") (pin "27") (pinfunction "D6_27") (pintype "bidirectional"))
      (node (ref "U6") (pin "18") (pinfunction "D6_18") (pintype "bidirectional"))
      (node (ref "U7") (pin "18") (pinfunction "D6_18") (pintype "bidirectional"))
    )
    (net (code "34") (name "D7") (class "Default")
      (node (ref "J3") (pin "E") (pinfunction "E_E") (pintype "passive"))
      (node (ref "U4") (pin "26") (pinfunction "D7_26") (pintype "bidirectional"))
      (node (ref "U5") (pin "26") (pinfunction "D7_26") (pintype "bidirectional"))
      (node (ref "U6") (pin "19") (pinfunction "D7_19") (pintype "bidirectional"))
      (node (ref "U7") (pin "19") (pinfunction "D7_19") (pintype "bidirectional"))
    )
    (net (code "35") (name "DA") (class "Default")
      (node (ref "U5") (pin "17") (pinfunction "PB7_17") (pintype "bidirectional"))
      (node (ref "U8") (pin "39") (pinfunction "P39_39") (pintype "bidirectional"))
    )
    (net (code "36") (name "FIFO_DATA0") (class "Default")
      (node (ref "U1") (pin "24") (pinfunction "DATA0_24") (pintype "bidirectional"))
      (node (ref "U8") (pin "13") (pinfunction "P13_13") (pintype "bidirectional"))
    )
    (net (code "37") (name "FIFO_DATA1") (class "Default")
      (node (ref "U1") (pin "4") (pinfunction "DATA1_4") (pintype "bidirectional"))
      (node (ref "U8") (pin "9") (pinfunction "P9_9") (pintype "bidirectional"))
    )
    (net (code "38") (name "FIFO_DATA2") (class "Default")
      (node (ref "U1") (pin "2") (pinfunction "DATA2_2") (pintype "bidirectional"))
      (node (ref "U8") (pin "11") (pinfunction "P11_11") (pintype "bidirectional"))
    )
    (net (code "39") (name "FIFO_DATA3") (class "Default")
      (node (ref "U1") (pin "9") (pinfunction "DATA3_9") (pintype "bidirectional"))
      (node (ref "U8") (pin "4") (pinfunction "P4_4") (pintype "bidirectional"))
    )
    (net (code "40") (name "FIFO_DATA4") (class "Default")
      (node (ref "U1") (pin "1") (pinfunction "DATA4_1") (pintype "bidirectional"))
      (node (ref "U8") (pin "12") (pinfunction "P12_12") (pintype "bidirectional"))
    )
    (net (code "41") (name "FIFO_DATA5") (class "Default")
      (node (ref "U1") (pin "7") (pinfunction "DATA5_7") (pintype "bidirectional"))
      (node (ref "U8") (pin "6") (pinfunction "P6_6") (pintype "bidirectional"))
    )
    (net (code "42") (name "FIFO_DATA6") (class "Default")
      (node (ref "U1") (pin "8") (pinfunction "DATA6_8") (pintype "bidirectional"))
      (node (ref "U8") (pin "5") (pinfunction "P5/GTS1_5") (pintype "bidirectional"))
    )
    (net (code "43") (name "FIFO_DATA7") (class "Default")
      (node (ref "U1") (pin "5") (pinfunction "DATA7_5") (pintype "bidirectional"))
      (node (ref "U8") (pin "7") (pinfunction "P7_7") (pintype "bidirectional"))
    )
    (net (code "44") (name "FIFO_RD") (class "Default")
      (node (ref "U1") (pin "11") (pinfunction "~{RD}_11") (pintype "input"))
      (node (ref "U8") (pin "2") (pinfunction "P2/GTS2_2") (pintype "bidirectional"))
    )
    (net (code "45") (name "FIFO_RXF") (class "Default")
      (node (ref "U1") (pin "21") (pinfunction "~{RXF}_21") (pintype "output"))
      (node (ref "U8") (pin "10") (pinfunction "P10_10") (pintype "bidirectional"))
    )
    (net (code "46") (name "FIFO_TXE") (class "Default")
      (node (ref "U1") (pin "20") (pinfunction "~{TXE}_20") (pintype "output"))
      (node (ref "U8") (pin "8") (pinfunction "P8_8") (pintype "bidirectional"))
    )
    (net (code "47") (name "FIFO_WR") (class "Default")
      (node (ref "U1") (pin "12") (pinfunction "~{WR}_12") (pintype "input"))
      (node (ref "U8") (pin "1") (pinfunction "P1_1") (pintype "bidirectional"))
    )
    (net (code "48") (name "GND") (class "Default")
      (node (ref "C1") (pin "2") (pinfunction "2_2") (pintype "passive"))
      (node (ref "C10") (pin "2") (pinfunction "2_2") (pintype "passive"))
      (node (ref "C11") (pin "2") (pinfunction "2_2") (pintype "passive"))
      (node (ref "C12") (pin "2") (pinfunction "2_2") (pintype "passive"))
      (node (ref "C13") (pin "2") (pinfunction "2_2") (pintype "passive"))
      (node (ref "C14") (pin "2") (pinfunction "2_2") (pintype "passive"))
      (node (ref "C15") (pin "2") (pinfunction "2_2") (pintype "passive"))
      (node (ref "C2") (pin "2") (pinfunction "2_2") (pintype "passive"))
      (node (ref "C3") (pin "2") (pinfunction "2_2") (pintype "passive"))
      (node (ref "C4") (pin "2") (pinfunction "2_2") (pintype "passive"))
      (node (ref "C5") (pin "2") (pinfunction "2_2") (pintype "passive"))
      (node (ref "C6") (pin "2") (pinfunction "2_2") (pintype "passive"))
      (node (ref "C7") (pin "2") (pinfunction "2_2") (pintype "passive"))
      (node (ref "C8") (pin "2") (pinfunction "2_2") (pintype "passive"))
      (node (ref "C9") (pin "2") (pinfunction "2_2") (pintype "passive"))
      (node (ref "CLEAR") (pin "3") (pinfunction "2_3") (pintype "passive"))
      (node (ref "CLEAR") (pin "4") (pinfunction "2_4") (pintype "passive"))
      (node (ref "J1") (pin "5") (pinfunction "5_5") (pintype "power_in"))
      (node (ref "J1") (pin "6") (pinfunction "5_6") (pintype "power_in"))
      (node (ref "J1") (pin "7") (pinfunction "5_7") (pintype "power_in"))
      (node (ref "J1") (pin "8") (pinfunction "5_8") (pintype "power_in"))
      (node (ref "J1") (pin "9") (pinfunction "5_9") (pintype "power_in"))
      (node (ref "J2") (pin "11") (pinfunction "GND_11") (pintype "power_in"))
      (node (ref "J2") (pin "3") (pinfunction "GND_3") (pintype "power_in"))
      (node (ref "J2") (pin "5") (pinfunction "GND_5") (pintype "power_in"))
      (node (ref "J2") (pin "7") (pinfunction "GND_7") (pintype "power_in"))
      (node (ref "J2") (pin "9") (pinfunction "GND_9") (pintype "power_in"))
      (node (ref "J3") (pin "20") (pinfunction "20_20") (pintype "passive"))
      (node (ref "J3") (pin "X") (pinfunction "X_X") (pintype "passive"))
      (node (ref "R8") (pin "1") (pinfunction "1_1") (pintype "passive"))
      (node (ref "RESET") (pin "3") (pinfunction "2_3") (pintype "passive"))
      (node (ref "RESET") (pin "4") (pinfunction "2_4") (pintype "passive"))
      (node (ref "U1") (pin "19") (pinfunction "GND_19") (pintype "power_in"))
      (node (ref "U1") (pin "6") (pinfunction "GND_6") (pintype "power_in"))
      (node (ref "U2") (pin "2") (pinfunction "GND_2") (pintype "power_in"))
      (node (ref "U3") (pin "1") (pinfunction "GND_1") (pintype "power_in"))
      (node (ref "U4") (pin "1") (pinfunction "GND_1") (pintype "power_in"))
      (node (ref "U4") (pin "21") (pinfunction "GND_21") (pintype "power_in"))
      (node (ref "U4") (pin "38") (pinfunction "~{SO}_38") (pintype "input"))
      (node (ref "U5") (pin "1") (pinfunction "GND_1") (pintype "power_in"))
      (node (ref "U6") (pin "14") (pinfunction "GND_14") (pintype "power_in"))
      (node (ref "U7") (pin "14") (pinfunction "GND_14") (pintype "power_in"))
      (node (ref "U8") (pin "14") (pinfunction "GND_14") (pintype "power_in"))
      (node (ref "U8") (pin "15") (pinfunction "P15/GCK1_15") (pintype "bidirectional"))
      (node (ref "U8") (pin "18") (pinfunction "P18_18") (pintype "bidirectional"))
      (node (ref "U8") (pin "20") (pinfunction "P20_20") (pintype "bidirectional"))
      (node (ref "U8") (pin "21") (pinfunction "GND_21") (pintype "power_in"))
      (node (ref "U8") (pin "27") (pinfunction "P27_27") (pintype "bidirectional"))
      (node (ref "U8") (pin "36") (pinfunction "P36_36") (pintype "bidirectional"))
      (node (ref "U8") (pin "41") (pinfunction "GND_41") (pintype "power_in"))
      (node (ref "U8") (pin "54") (pinfunction "GND_54") (pintype "power_in"))
      (node (ref "U8") (pin "62") (pinfunction "P62_62") (pintype "bidirectional"))
    )
    (net (code "49") (name "IRQ") (class "Default")
      (node (ref "J3") (pin "4") (pinfunction "4_4") (pintype "passive"))
      (node (ref "R11") (pin "1") (pinfunction "1_1") (pintype "passive"))
      (node (ref "U4") (pin "4") (pinfunction "~{IRQ}_4") (pintype "input"))
    )
    (net (code "50") (name "NMI") (class "Default")
      (node (ref "J3") (pin "3") (pinfunction "3_3") (pintype "passive"))
      (node (ref "R12") (pin "1") (pinfunction "1_1") (pintype "passive"))
      (node (ref "U4") (pin "6") (pinfunction "~{NMI}_6") (pintype "input"))
    )
    (net (code "51") (name "Net-(CLEAR-1-Pad2)") (class "Default")
      (node (ref "CLEAR") (pin "1") (pinfunction "1_1") (pintype "passive"))
      (node (ref "CLEAR") (pin "2") (pinfunction "1_2") (pintype "passive"))
      (node (ref "R6") (pin "1") (pinfunction "1_1") (pintype "passive"))
    )
    (net (code "52") (name "Net-(D1-Pad1)") (class "Default")
      (node (ref "D1") (pin "1") (pinfunction "1_1") (pintype "passive"))
      (node (ref "R8") (pin "2") (pinfunction "2_2") (pintype "passive"))
    )
    (net (code "53") (name "Net-(J1-Pad2)") (class "Default")
      (node (ref "J1") (pin "2") (pinfunction "2_2") (pintype "bidirectional"))
      (node (ref "R1") (pin "1") (pinfunction "1_1") (pintype "passive"))
    )
    (net (code "54") (name "Net-(J1-Pad3)") (class "Default")
      (node (ref "J1") (pin "3") (pinfunction "3_3") (pintype "bidirectional"))
      (node (ref "R2") (pin "1") (pinfunction "1_1") (pintype "passive"))
    )
    (net (code "55") (name "Net-(R7-Pad1)") (class "Default")
      (node (ref "R7") (pin "1") (pinfunction "1_1") (pintype "passive"))
      (node (ref "RESET") (pin "1") (pinfunction "1_1") (pintype "passive"))
      (node (ref "RESET") (pin "2") (pinfunction "1_2") (pintype "passive"))
    )
    (net (code "56") (name "Net-(U1A-USBDM)") (class "Default")
      (node (ref "R1") (pin "2") (pinfunction "2_2") (pintype "passive"))
      (node (ref "U1") (pin "14") (pinfunction "USBDM_14") (pintype "input"))
    )
    (net (code "57") (name "Net-(U1A-USBDP)") (class "Default")
      (node (ref "R2") (pin "2") (pinfunction "2_2") (pintype "passive"))
      (node (ref "U1") (pin "13") (pinfunction "USBDP_13") (pintype "input"))
    )
    (net (code "58") (name "Net-(U2A-A)") (class "Default")
      (node (ref "C5") (pin "1") (pinfunction "1_1") (pintype "passive"))
      (node (ref "R5") (pin "1") (pinfunction "1_1") (pintype "passive"))
      (node (ref "R7") (pin "2") (pinfunction "2_2") (pintype "passive"))
      (node (ref "U2") (pin "1") (pinfunction "A_1") (pintype "input"))
    )
    (net (code "59") (name "Net-(U2B-A)") (class "Default")
      (node (ref "C4") (pin "1") (pinfunction "1_1") (pintype "passive"))
      (node (ref "R4") (pin "1") (pinfunction "1_1") (pintype "passive"))
      (node (ref "R6") (pin "2") (pinfunction "2_2") (pintype "passive"))
      (node (ref "U2") (pin "3") (pinfunction "A_3") (pintype "input"))
    )
    (net (code "60") (name "PA0") (class "Default")
      (node (ref "U5") (pin "2") (pinfunction "PA0_2") (pintype "bidirectional"))
      (node (ref "U8") (pin "50") (pinfunction "P50_50") (pintype "bidirectional"))
    )
    (net (code "61") (name "PA1") (class "Default")
      (node (ref "U5") (pin "3") (pinfunction "PA1_3") (pintype "bidirectional"))
      (node (ref "U8") (pin "52") (pinfunction "P52_52") (pintype "bidirectional"))
    )
    (net (code "62") (name "PA2") (class "Default")
      (node (ref "U5") (pin "4") (pinfunction "PA2_4") (pintype "bidirectional"))
      (node (ref "U8") (pin "57") (pinfunction "P57_57") (pintype "bidirectional"))
    )
    (net (code "63") (name "PA3") (class "Default")
      (node (ref "U5") (pin "5") (pinfunction "PA3_5") (pintype "bidirectional"))
      (node (ref "U8") (pin "59") (pinfunction "P59_59") (pintype "bidirectional"))
    )
    (net (code "64") (name "PA4") (class "Default")
      (node (ref "U5") (pin "6") (pinfunction "PA4_6") (pintype "bidirectional"))
      (node (ref "U8") (pin "58") (pinfunction "P58_58") (pintype "bidirectional"))
    )
    (net (code "65") (name "PA5") (class "Default")
      (node (ref "U5") (pin "7") (pinfunction "PA5_7") (pintype "bidirectional"))
      (node (ref "U8") (pin "60") (pinfunction "P60_60") (pintype "bidirectional"))
    )
    (net (code "66") (name "PA6") (class "Default")
      (node (ref "U5") (pin "8") (pinfunction "PA6_8") (pintype "bidirectional"))
      (node (ref "U8") (pin "61") (pinfunction "P61_61") (pintype "bidirectional"))
    )
    (net (code "67") (name "PB0") (class "Default")
      (node (ref "U5") (pin "10") (pinfunction "PB0_10") (pintype "bidirectional"))
      (node (ref "U8") (pin "47") (pinfunction "P47_47") (pintype "bidirectional"))
    )
    (net (code "68") (name "PB1") (class "Default")
      (node (ref "U5") (pin "11") (pinfunction "PB1_11") (pintype "bidirectional"))
      (node (ref "U8") (pin "46") (pinfunction "P46_46") (pintype "bidirectional"))
    )
    (net (code "69") (name "PB2") (class "Default")
      (node (ref "U5") (pin "12") (pinfunction "PB2_12") (pintype "bidirectional"))
      (node (ref "U8") (pin "45") (pinfunction "P45_45") (pintype "bidirectional"))
    )
    (net (code "70") (name "PB3") (class "Default")
      (node (ref "U5") (pin "13") (pinfunction "PB3_13") (pintype "bidirectional"))
      (node (ref "U8") (pin "44") (pinfunction "P44_44") (pintype "bidirectional"))
    )
    (net (code "71") (name "PB4") (class "Default")
      (node (ref "U5") (pin "14") (pinfunction "PB4_14") (pintype "bidirectional"))
      (node (ref "U8") (pin "43") (pinfunction "P43_43") (pintype "bidirectional"))
    )
    (net (code "72") (name "PB5") (class "Default")
      (node (ref "U5") (pin "15") (pinfunction "PB5_15") (pintype "bidirectional"))
      (node (ref "U8") (pin "42") (pinfunction "P42_42") (pintype "bidirectional"))
    )
    (net (code "73") (name "PB6") (class "Default")
      (node (ref "U5") (pin "16") (pinfunction "PB6_16") (pintype "bidirectional"))
      (node (ref "U8") (pin "40") (pinfunction "P40_40") (pintype "bidirectional"))
    )
    (net (code "74") (name "PHI0") (class "Default")
      (node (ref "J3") (pin "M") (pinfunction "M_M") (pintype "passive"))
      (node (ref "U4") (pin "37") (pinfunction "PHI0_37") (pintype "input"))
      (node (ref "U8") (pin "17") (pinfunction "P17/GCK3_17") (pintype "bidirectional"))
    )
    (net (code "75") (name "PHI1") (class "Default")
      (node (ref "J3") (pin "D") (pinfunction "D_D") (pintype "passive"))
      (node (ref "U4") (pin "3") (pinfunction "PHI1_3") (pintype "output"))
    )
    (net (code "76") (name "PHI2") (class "Default")
      (node (ref "J3") (pin "A") (pinfunction "A_A") (pintype "passive"))
      (node (ref "U4") (pin "39") (pinfunction "PHI2_39") (pintype "output"))
      (node (ref "U5") (pin "25") (pinfunction "E_25") (pintype "input"))
      (node (ref "U8") (pin "19") (pinfunction "P19_19") (pintype "bidirectional"))
    )
    (net (code "77") (name "PWREN") (class "Default")
      (node (ref "R9") (pin "1") (pinfunction "1_1") (pintype "passive"))
      (node (ref "U1") (pin "22") (pinfunction "CBUS6_22") (pintype "bidirectional"))
      (node (ref "U3") (pin "4") (pinfunction "~{EN1}_4") (pintype "input"))
      (node (ref "U3") (pin "5") (pinfunction "~{EN2}_5") (pintype "input"))
    )
    (net (code "78") (name "R") (class "Default")
      (node (ref "J3") (pin "L") (pinfunction "L_L") (pintype "passive"))
      (node (ref "U8") (pin "23") (pinfunction "P23_23") (pintype "bidirectional"))
    )
    (net (code "79") (name "RDY") (class "Default")
      (node (ref "J3") (pin "5") (pinfunction "5_5") (pintype "passive"))
      (node (ref "R10") (pin "1") (pinfunction "1_1") (pintype "passive"))
      (node (ref "U4") (pin "2") (pinfunction "RDY_2") (pintype "input"))
    )
    (net (code "80") (name "RESET") (class "Default")
      (node (ref "J3") (pin "2") (pinfunction "2_2") (pintype "passive"))
      (node (ref "U2") (pin "6") (pinfunction "Y_6") (pintype "output"))
      (node (ref "U4") (pin "40") (pinfunction "~{RESET}_40") (pintype "input"))
      (node (ref "U5") (pin "34") (pinfunction "~{RESET}_34") (pintype "input"))
      (node (ref "U8") (pin "48") (pinfunction "P48_48") (pintype "bidirectional"))
    )
    (net (code "81") (name "RW") (class "Default")
      (node (ref "J3") (pin "K") (pinfunction "K_K") (pintype "passive"))
      (node (ref "U4") (pin "34") (pinfunction "R/~{W}_34") (pintype "output"))
      (node (ref "U5") (pin "21") (pinfunction "R/~{W}_21") (pintype "input"))
      (node (ref "U6") (pin "27") (pinfunction "~{WE}_27") (pintype "input"))
      (node (ref "U7") (pin "27") (pinfunction "~{WE}_27") (pintype "input"))
    )
    (net (code "82") (name "S") (class "Default")
      (node (ref "J3") (pin "11") (pinfunction "11_11") (pintype "passive"))
      (node (ref "U8") (pin "22") (pinfunction "P22_22") (pintype "bidirectional"))
    )
    (net (code "83") (name "SYNC") (class "Default")
      (node (ref "J3") (pin "B") (pinfunction "B_B") (pintype "passive"))
      (node (ref "U4") (pin "7") (pinfunction "SYNC_7") (pintype "output"))
    )
    (net (code "84") (name "T") (class "Default")
      (node (ref "J3") (pin "21") (pinfunction "21_21") (pintype "passive"))
      (node (ref "U8") (pin "31") (pinfunction "P31_31") (pintype "bidirectional"))
    )
    (net (code "85") (name "TCK") (class "Default")
      (node (ref "J2") (pin "6") (pinfunction "TCK_6") (pintype "output"))
      (node (ref "R3") (pin "1") (pinfunction "1_1") (pintype "passive"))
      (node (ref "U8") (pin "30") (pinfunction "TCK_30") (pintype "input"))
    )
    (net (code "86") (name "TDI") (class "Default")
      (node (ref "J2") (pin "10") (pinfunction "TDI_10") (pintype "output"))
      (node (ref "U8") (pin "28") (pinfunction "TDI_28") (pintype "input"))
    )
    (net (code "87") (name "TDO") (class "Default")
      (node (ref "J2") (pin "8") (pinfunction "TDO_8") (pintype "input"))
      (node (ref "U8") (pin "53") (pinfunction "TDO_53") (pintype "output"))
    )
    (net (code "88") (name "TMS") (class "Default")
      (node (ref "J2") (pin "4") (pinfunction "TMS_4") (pintype "output"))
      (node (ref "U8") (pin "29") (pinfunction "TMS_29") (pintype "input"))
    )
    (net (code "89") (name "VCORE") (class "Default")
      (node (ref "U1") (pin "17") (pinfunction "VCORE_17") (pintype "power_in"))
    )
    (net (code "90") (name "X") (class "Default")
      (node (ref "U6") (pin "20") (pinfunction "~{CE}_20") (pintype "input"))
      (node (ref "U6") (pin "22") (pinfunction "~{OE}_22") (pintype "input"))
      (node (ref "U8") (pin "32") (pinfunction "P32_32") (pintype "bidirectional"))
    )
    (net (code "91") (name "Y") (class "Default")
      (node (ref "U7") (pin "20") (pinfunction "~{CE}_20") (pintype "input"))
      (node (ref "U7") (pin "22") (pinfunction "~{OE}_22") (pintype "input"))
      (node (ref "U8") (pin "25") (pinfunction "P25_25") (pintype "bidirectional"))
    )
    (net (code "92") (name "Z") (class "Default")
      (node (ref "U5") (pin "23") (pinfunction "~{CS2}_23") (pintype "input"))
      (node (ref "U8") (pin "24") (pinfunction "P24_24") (pintype "bidirectional"))
    )
    (net (code "93") (name "unconnected-(J1-Pad4)") (class "Default")
      (node (ref "J1") (pin "4") (pinfunction "4_4") (pintype "passive"))
    )
    (net (code "94") (name "unconnected-(J3-Pad1)") (class "Default")
      (node (ref "J3") (pin "1") (pinfunction "1_1") (pintype "passive"))
    )
    (net (code "95") (name "unconnected-(J3-Pad10)") (class "Default")
      (node (ref "J3") (pin "10") (pinfunction "10_10") (pintype "passive"))
    )
    (net (code "96") (name "unconnected-(J3-PadC)") (class "Default")
      (node (ref "J3") (pin "C") (pinfunction "C_C") (pintype "passive"))
    )
    (net (code "97") (name "unconnected-(J3-PadY)") (class "Default")
      (node (ref "J3") (pin "Y") (pinfunction "Y_Y") (pintype "passive"))
    )
    (net (code "98") (name "unconnected-(J3-PadZ)") (class "Default")
      (node (ref "J3") (pin "Z") (pinfunction "Z_Z") (pintype "passive"))
    )
    (net (code "99") (name "unconnected-(U3-~{OC}-Pad8)") (class "Default")
      (node (ref "U3") (pin "8") (pinfunction "~{OC}_8") (pintype "output"))
    )
    (net (code "100") (name "unconnected-(U5A-~{IRQA}-Pad38)") (class "Default")
      (node (ref "U5") (pin "38") (pinfunction "~{IRQA}_38") (pintype "output"))
    )
    (net (code "101") (name "unconnected-(U5A-~{IRQB}-Pad37)") (class "Default")
      (node (ref "U5") (pin "37") (pinfunction "~{IRQB}_37") (pintype "output"))
    )
  )
)
